# appleii.net
KiCad netlist of a schematic drawn in EAGLE
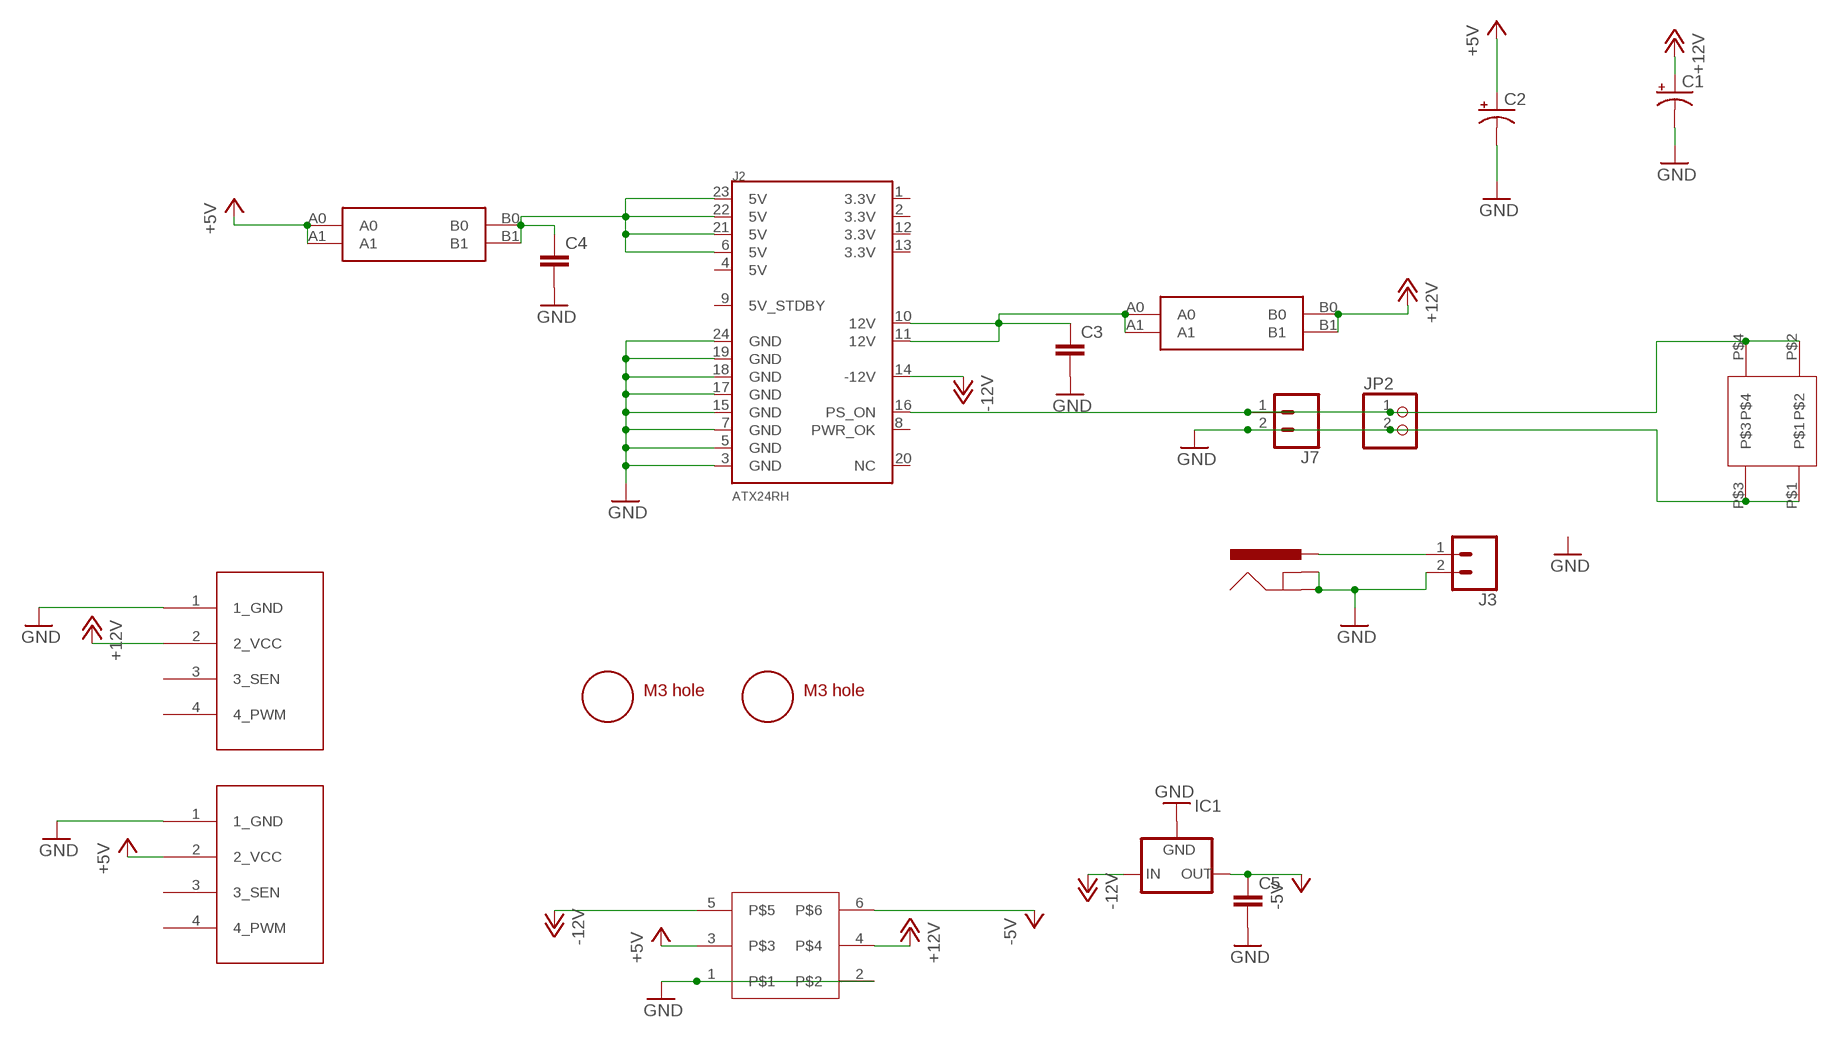
[diagram p0: schematic, sheet 1]

(export (version "E")
  (design (tool "Eeschema 10.0.6"))
  (components
    (comp (ref "C1")
      (value "CPOL-USE5-10.5")
      (footprint "eagle-import:E5-10,5")
      (libsource (lib "eagle-import") (part "CPOL-USE5-10.5"))
    )
    (comp (ref "C2")
      (value "CPOL-USE5-10.5")
      (footprint "eagle-import:E5-10,5")
      (libsource (lib "eagle-import") (part "CPOL-USE5-10.5"))
    )
    (comp (ref "C3")
      (value "C5/2.5")
      (footprint "eagle-import:C5B2.5")
      (libsource (lib "eagle-import") (part "C5/2.5"))
    )
    (comp (ref "C4")
      (value "C5/2.5")
      (footprint "eagle-import:C5B2.5")
      (libsource (lib "eagle-import") (part "C5/2.5"))
    )
    (comp (ref "C5")
      (value "C5/2.5")
      (footprint "eagle-import:C5B2.5")
      (libsource (lib "eagle-import") (part "C5/2.5"))
    )
    (comp (ref "IC1")
      (value "79XXS")
      (footprint "eagle-import:79XXS")
      (libsource (lib "eagle-import") (part "79XXS"))
    )
    (comp (ref "J1")
      (value "POWER_JACKPTH")
      (footprint "eagle-import:POWER_JACK_PTH")
      (libsource (lib "eagle-import") (part "POWER_JACKPTH"))
    )
    (comp (ref "J2")
      (value "ATX24RH")
      (footprint "eagle-import:ATX24_RIGHT_ANGLE")
      (libsource (lib "eagle-import") (part "ATX24RH"))
    )
    (comp (ref "J3")
      (value "CONN_023.5MM-NO_SILK")
      (footprint "eagle-import:SCREWTERMINAL-3.5MM-2-NS")
      (libsource (lib "eagle-import") (part "CONN_023.5MM-NO_SILK"))
    )
    (comp (ref "J7")
      (value "CONN_023.5MM-NO_SILK")
      (footprint "eagle-import:SCREWTERMINAL-3.5MM-2-NS")
      (libsource (lib "eagle-import") (part "CONN_023.5MM-NO_SILK"))
    )
    (comp (ref "JP1")
      (value "4PIN_FAN")
      (footprint "eagle-import:1X04")
      (libsource (lib "eagle-import") (part "4PIN_FAN"))
    )
    (comp (ref "JP2")
      (value "PINHD-1X2")
      (footprint "eagle-import:1X02")
      (libsource (lib "eagle-import") (part "PINHD-1X2"))
    )
    (comp (ref "JP4")
      (value "4PIN_FAN")
      (footprint "eagle-import:1X04")
      (libsource (lib "eagle-import") (part "4PIN_FAN"))
    )
    (comp (ref "U$1")
      (value "M3_MOUNTING_HOLE")
      (footprint "eagle-import:M3_MOUNTING_HOLE_PACK")
      (libsource (lib "eagle-import") (part "M3_MOUNTING_HOLE"))
    )
    (comp (ref "U$2")
      (value "CAR_FUSE_HOLDER3IN1")
      (footprint "eagle-import:FUSE_HOLDER_3IN1")
      (libsource (lib "eagle-import") (part "CAR_FUSE_HOLDER3IN1"))
    )
    (comp (ref "U$3")
      (value "M3_MOUNTING_HOLE")
      (footprint "eagle-import:M3_MOUNTING_HOLE_PACK")
      (libsource (lib "eagle-import") (part "M3_MOUNTING_HOLE"))
    )
    (comp (ref "U$4")
      (value "APPLEII")
      (footprint "eagle-import:APPLEII")
      (libsource (lib "eagle-import") (part "APPLEII"))
    )
    (comp (ref "U$5")
      (value "ROCK_SW")
      (footprint "eagle-import:ROCK_SWITCH")
      (libsource (lib "eagle-import") (part "ROCK_SW"))
    )
    (comp (ref "U$8")
      (value "CAR_FUSE_HOLDER3IN1")
      (footprint "eagle-import:FUSE_HOLDER_3IN1")
      (libsource (lib "eagle-import") (part "CAR_FUSE_HOLDER3IN1"))
    )
  )
  (nets
    (net (code "1") (name "+5V") (class "Default")
      (node (ref "C2") (pin "+") (pinfunction "+_+") (pintype "passive"))
      (node (ref "JP4") (pin "2") (pinfunction "2_VCC_2") (pintype "passive"))
      (node (ref "U$4") (pin "3") (pinfunction "P$3_3") (pintype "bidirectional"))
      (node (ref "U$8") (pin "A0") (pinfunction "A0_A0") (pintype "bidirectional"))
      (node (ref "U$8") (pin "A1") (pinfunction "A1_A1") (pintype "bidirectional"))
    )
    (net (code "2") (name "+12V") (class "Default")
      (node (ref "C1") (pin "+") (pinfunction "+_+") (pintype "passive"))
      (node (ref "JP1") (pin "2") (pinfunction "2_VCC_2") (pintype "passive"))
      (node (ref "U$2") (pin "B0") (pinfunction "B0_B0") (pintype "bidirectional"))
      (node (ref "U$2") (pin "B1") (pinfunction "B1_B1") (pintype "bidirectional"))
      (node (ref "U$4") (pin "4") (pinfunction "P$4_4") (pintype "bidirectional"))
    )
    (net (code "3") (name "-5V") (class "Default")
      (node (ref "C5") (pin "1") (pinfunction "1_1") (pintype "passive"))
      (node (ref "IC1") (pin "OUT") (pinfunction "OUT_OUT") (pintype "passive"))
      (node (ref "U$4") (pin "6") (pinfunction "P$6_6") (pintype "bidirectional"))
    )
    (net (code "4") (name "-12V") (class "Default")
      (node (ref "IC1") (pin "IN") (pinfunction "IN_IN") (pintype "input"))
      (node (ref "J2") (pin "14") (pinfunction "-12V_14") (pintype "bidirectional"))
      (node (ref "U$4") (pin "5") (pinfunction "P$5_5") (pintype "bidirectional"))
    )
    (net (code "5") (name "GND") (class "Default")
      (node (ref "C1") (pin "-") (pinfunction "-_-") (pintype "passive"))
      (node (ref "C2") (pin "-") (pinfunction "-_-") (pintype "passive"))
      (node (ref "C3") (pin "2") (pinfunction "2_2") (pintype "passive"))
      (node (ref "C4") (pin "2") (pinfunction "2_2") (pintype "passive"))
      (node (ref "C5") (pin "2") (pinfunction "2_2") (pintype "passive"))
      (node (ref "IC1") (pin "GND") (pinfunction "GND_GND") (pintype "input"))
      (node (ref "J1") (pin "GND") (pinfunction "GND_GND") (pintype "bidirectional"))
      (node (ref "J1") (pin "GNDBREAK") (pinfunction "GNDBREAK_GNDBREAK") (pintype "bidirectional"))
      (node (ref "J2") (pin "15") (pinfunction "GND_15") (pintype "bidirectional"))
      (node (ref "J2") (pin "17") (pinfunction "GND_17") (pintype "bidirectional"))
      (node (ref "J2") (pin "18") (pinfunction "GND_18") (pintype "bidirectional"))
      (node (ref "J2") (pin "19") (pinfunction "GND_19") (pintype "bidirectional"))
      (node (ref "J2") (pin "24") (pinfunction "GND_24") (pintype "bidirectional"))
      (node (ref "J2") (pin "3") (pinfunction "GND_3") (pintype "bidirectional"))
      (node (ref "J2") (pin "5") (pinfunction "GND_5") (pintype "bidirectional"))
      (node (ref "J2") (pin "7") (pinfunction "GND_7") (pintype "bidirectional"))
      (node (ref "J3") (pin "2") (pinfunction "2_2") (pintype "passive"))
      (node (ref "J7") (pin "2") (pinfunction "2_2") (pintype "passive"))
      (node (ref "JP1") (pin "1") (pinfunction "1_GND_1") (pintype "passive"))
      (node (ref "JP2") (pin "2") (pinfunction "2_2") (pintype "passive"))
      (node (ref "JP4") (pin "1") (pinfunction "1_GND_1") (pintype "passive"))
      (node (ref "U$4") (pin "1") (pinfunction "P$1_1") (pintype "bidirectional"))
      (node (ref "U$4") (pin "2") (pinfunction "P$2_2") (pintype "bidirectional"))
      (node (ref "U$5") (pin "P$1") (pinfunction "P$1_P$1") (pintype "bidirectional"))
      (node (ref "U$5") (pin "P$3") (pinfunction "P$3_P$3") (pintype "bidirectional"))
    )
    (net (code "6") (name "Net-(C3-Pad1)") (class "Default")
      (node (ref "C3") (pin "1") (pinfunction "1_1") (pintype "passive"))
      (node (ref "J2") (pin "10") (pinfunction "12V_10") (pintype "bidirectional"))
      (node (ref "J2") (pin "11") (pinfunction "12V_11") (pintype "bidirectional"))
      (node (ref "U$2") (pin "A0") (pinfunction "A0_A0") (pintype "bidirectional"))
      (node (ref "U$2") (pin "A1") (pinfunction "A1_A1") (pintype "bidirectional"))
    )
    (net (code "7") (name "Net-(C4-Pad1)") (class "Default")
      (node (ref "C4") (pin "1") (pinfunction "1_1") (pintype "passive"))
      (node (ref "J2") (pin "21") (pinfunction "5V_21") (pintype "bidirectional"))
      (node (ref "J2") (pin "22") (pinfunction "5V_22") (pintype "bidirectional"))
      (node (ref "J2") (pin "23") (pinfunction "5V_23") (pintype "bidirectional"))
      (node (ref "J2") (pin "6") (pinfunction "5V_6") (pintype "bidirectional"))
      (node (ref "U$8") (pin "B0") (pinfunction "B0_B0") (pintype "bidirectional"))
      (node (ref "U$8") (pin "B1") (pinfunction "B1_B1") (pintype "bidirectional"))
    )
    (net (code "8") (name "Net-(J1-PadPWR)") (class "Default")
      (node (ref "J1") (pin "PWR") (pinfunction "PWR_PWR") (pintype "bidirectional"))
      (node (ref "J3") (pin "1") (pinfunction "1_1") (pintype "passive"))
    )
    (net (code "9") (name "Net-(J2-PS_ON)") (class "Default")
      (node (ref "J2") (pin "16") (pinfunction "PS_ON_16") (pintype "bidirectional"))
      (node (ref "J7") (pin "1") (pinfunction "1_1") (pintype "passive"))
      (node (ref "JP2") (pin "1") (pinfunction "1_1") (pintype "passive"))
      (node (ref "U$5") (pin "P$2") (pinfunction "P$2_P$2") (pintype "bidirectional"))
      (node (ref "U$5") (pin "P$4") (pinfunction "P$4_P$4") (pintype "bidirectional"))
    )
    (net (code "10") (name "unconnected-(J2-3.3V-Pad1)") (class "Default")
      (node (ref "J2") (pin "1") (pinfunction "3.3V_1") (pintype "bidirectional"))
    )
    (net (code "11") (name "unconnected-(J2-3.3V-Pad2)") (class "Default")
      (node (ref "J2") (pin "2") (pinfunction "3.3V_2") (pintype "bidirectional"))
    )
    (net (code "12") (name "unconnected-(J2-3.3V-Pad12)") (class "Default")
      (node (ref "J2") (pin "12") (pinfunction "3.3V_12") (pintype "bidirectional"))
    )
    (net (code "13") (name "unconnected-(J2-3.3V-Pad13)") (class "Default")
      (node (ref "J2") (pin "13") (pinfunction "3.3V_13") (pintype "bidirectional"))
    )
    (net (code "14") (name "unconnected-(J2-5V-Pad4)") (class "Default")
      (node (ref "J2") (pin "4") (pinfunction "5V_4") (pintype "bidirectional"))
    )
    (net (code "15") (name "unconnected-(J2-5V_STDBY-Pad9)") (class "Default")
      (node (ref "J2") (pin "9") (pinfunction "5V_STDBY_9") (pintype "bidirectional"))
    )
    (net (code "16") (name "unconnected-(J2-NC-Pad20)") (class "Default")
      (node (ref "J2") (pin "20") (pinfunction "NC_20") (pintype "bidirectional"))
    )
    (net (code "17") (name "unconnected-(J2-PWR_OK-Pad8)") (class "Default")
      (node (ref "J2") (pin "8") (pinfunction "PWR_OK_8") (pintype "bidirectional"))
    )
    (net (code "18") (name "unconnected-(JP1-3_SEN-Pad3)") (class "Default")
      (node (ref "JP1") (pin "3") (pinfunction "3_SEN_3") (pintype "passive"))
    )
    (net (code "19") (name "unconnected-(JP1-4_PWM-Pad4)") (class "Default")
      (node (ref "JP1") (pin "4") (pinfunction "4_PWM_4") (pintype "passive"))
    )
    (net (code "20") (name "unconnected-(JP4-3_SEN-Pad3)") (class "Default")
      (node (ref "JP4") (pin "3") (pinfunction "3_SEN_3") (pintype "passive"))
    )
    (net (code "21") (name "unconnected-(JP4-4_PWM-Pad4)") (class "Default")
      (node (ref "JP4") (pin "4") (pinfunction "4_PWM_4") (pintype "passive"))
    )
  )
)
